# Sheet2.net
KiCad netlist of a schematic drawn in Altium Designer
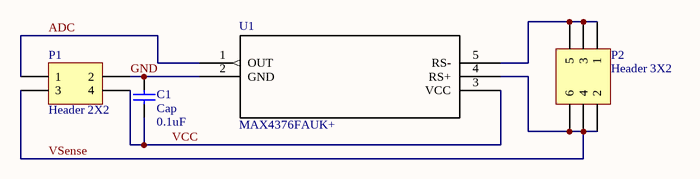
[diagram p0: Sheet2.SchDoc]

(export (version "E")
  (design (tool "Eeschema 10.0.6"))
  (components
    (comp (ref "C1")
      (value "Cap")
      (footprint "C1206")
      (description "Capacitor (Semiconductor SIM Model)")
      (fields (field (name "ALTIUM_VALUE") "0.1uF") (field (name "PUBLISHER") "Altium Limited"))
      (libsource (lib "Miscellaneous Devices") (part "Cap Semi"))
    )
    (comp (ref "P1")
      (value "Header 2X2")
      (footprint "HDR2X2")
      (description "Header, 2-Pin, Dual row")
      (fields (field (name "PUBLISHER") "Altium Limited"))
      (libsource (lib "Miscellaneous Connectors") (part "Header 2X2"))
    )
    (comp (ref "P2")
      (value "Header 3X2")
      (footprint "HDR2X3")
      (description "Header, 3-Pin, Dual row")
      (fields (field (name "PUBLISHER") "Altium Limited"))
      (libsource (lib "Miscellaneous Connectors") (part "Header 3X2"))
    )
    (comp (ref "U1")
      (value "MAX4376FAUK+")
      (footprint "21-0057F")
      (description "Imported")
      (fields (field (name "MANUFACTURER_PART_NUMBER") "max4376fauk+"))
      (libsource (lib "Schlib") (part "MAX4376FAUK+"))
    )
  )
  (nets
    (net (code "1") (name "/ADC") (class "Default")
      (node (ref "P1") (pin "1") (pinfunction "1_1") (pintype "passive"))
      (node (ref "U1") (pin "1") (pinfunction "OUT_1") (pintype "output"))
    )
    (net (code "2") (name "/GND") (class "Default")
      (node (ref "C1") (pin "2") (pinfunction "2_2") (pintype "passive"))
      (node (ref "P1") (pin "2") (pinfunction "2_2") (pintype "passive"))
      (node (ref "U1") (pin "2") (pinfunction "GND_2") (pintype "power_in"))
    )
    (net (code "3") (name "/VCC") (class "Default")
      (node (ref "C1") (pin "1") (pinfunction "1_1") (pintype "passive"))
      (node (ref "P1") (pin "4") (pinfunction "4_4") (pintype "passive"))
      (node (ref "U1") (pin "3") (pinfunction "VCC_3") (pintype "power_in"))
    )
    (net (code "4") (name "/VSense") (class "Default")
      (node (ref "P1") (pin "3") (pinfunction "3_3") (pintype "passive"))
      (node (ref "P2") (pin "2") (pinfunction "2_2") (pintype "passive"))
      (node (ref "P2") (pin "4") (pinfunction "4_4") (pintype "passive"))
      (node (ref "P2") (pin "6") (pinfunction "6_6") (pintype "passive"))
      (node (ref "U1") (pin "4") (pinfunction "RS+_4") (pintype "passive"))
    )
    (net (code "5") (name "Net-(U1-RS-)") (class "Default")
      (node (ref "P2") (pin "1") (pinfunction "1_1") (pintype "passive"))
      (node (ref "P2") (pin "3") (pinfunction "3_3") (pintype "passive"))
      (node (ref "P2") (pin "5") (pinfunction "5_5") (pintype "passive"))
      (node (ref "U1") (pin "5") (pinfunction "RS-_5") (pintype "passive"))
    )
  )
)
